# Fish_Feeder_Schematic.net
KiCad netlist of a schematic drawn in Altium Designer
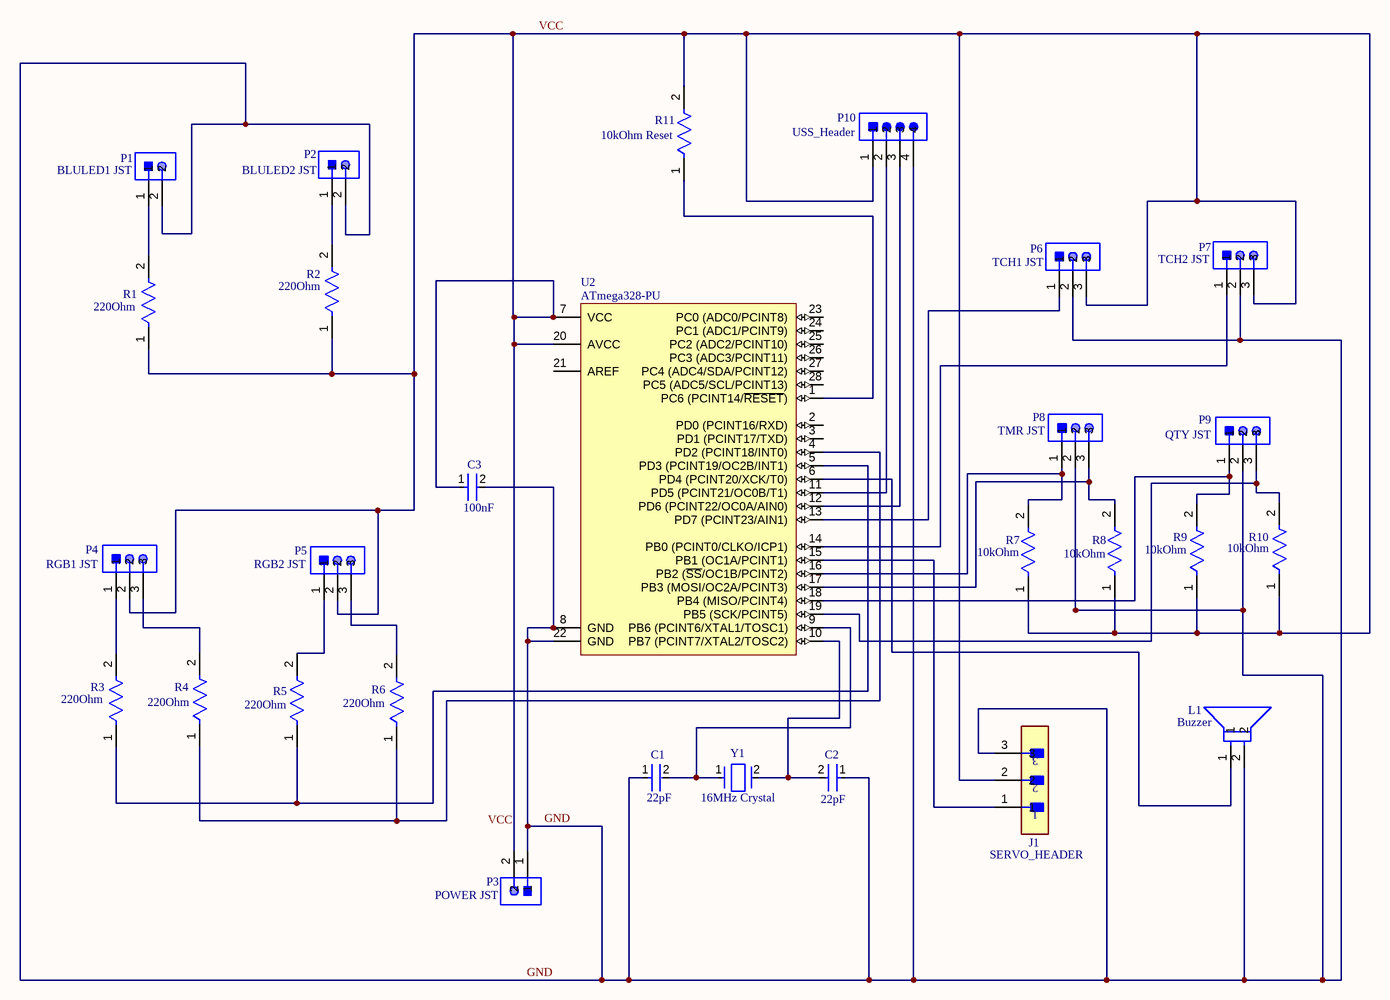
[diagram p0: Fish_Feeder_Schematic.SchDoc]

(export (version "E")
  (design (tool "Eeschema 10.0.6"))
  (components
    (comp (ref "C1")
      (value "22pF")
      (footprint "FP-VY1470-MFG")
      (description "CAP CER 2200PF 760VAC Y5U RADIAL")
      (fields (field (name "VOLTAGE") "500V") (field (name "TOLERANCE") "20%"))
      (libsource (lib "Altium Content Vault") (part "11868f565c42a9108669ba33697ecf6"))
    )
    (comp (ref "C2")
      (value "22pF")
      (footprint "FP-VY1470-MFG")
      (description "CAP CER 2200PF 760VAC Y5U RADIAL")
      (fields (field (name "VOLTAGE") "500V") (field (name "TOLERANCE") "20%"))
      (libsource (lib "Altium Content Vault") (part "11868f565c42a9108669ba33697ecf6"))
    )
    (comp (ref "C3")
      (value "100nF")
      (footprint "FP-VY1470-MFG")
      (description "CAP CER 2200PF 760VAC Y5U RADIAL")
      (fields (field (name "VOLTAGE") "500V") (field (name "TOLERANCE") "20%"))
      (libsource (lib "Altium Content Vault") (part "11868f565c42a9108669ba33697ecf6"))
    )
    (comp (ref "J1")
      (value "SERVO_HEADER")
      (footprint "FP-87224-3-MFG")
      (description "CONN HEADER VERT 3POS 2.54MM")
      (libsource (lib "Altium Content Vault") (part "0d3f023dd272f625e17a2be33dea85f"))
    )
    (comp (ref "L1")
      (value "Buzzer")
      (footprint "FP-PS1440P02BT-MFG")
      (description "AUDIO PIEZO TRANSDUCER 30V TH")
      (libsource (lib "Altium Content Vault") (part "5f581d31613f872430949aa526fd155"))
    )
    (comp (ref "P1")
      (value "BLULED1 JST")
      (footprint "JST-S2B-PH-K-S_V")
      (fields (field (name "TOLERANCE") "20%"))
      (libsource (lib "Altium Content Vault") (part "CN-1P-M-R2"))
    )
    (comp (ref "P2")
      (value "BLULED2 JST")
      (footprint "JST-S2B-PH-K-S_V")
      (fields (field (name "TOLERANCE") "20%"))
      (libsource (lib "Altium Content Vault") (part "CN-1P-M-R2"))
    )
    (comp (ref "P3")
      (value "POWER JST")
      (footprint "JST-S2B-PH-K-S_V")
      (fields (field (name "TOLERANCE") "20%"))
      (libsource (lib "") (part "CN-1P-M-R2_1"))
    )
    (comp (ref "P4")
      (value "RGB1 JST")
      (footprint "JST-B3B-PH-K-S-3_V")
      (fields (field (name "MANUFACTURER") "JST"))
      (libsource (lib "Altium Content Vault") (part "CN-1P-M-R3"))
    )
    (comp (ref "P5")
      (value "RGB2 JST")
      (footprint "JST-B3B-PH-K-S-3_V")
      (fields (field (name "MANUFACTURER") "JST"))
      (libsource (lib "Altium Content Vault") (part "CN-1P-M-R3"))
    )
    (comp (ref "P6")
      (value "TCH1 JST")
      (footprint "JST-B3B-PH-K-S-3_V")
      (fields (field (name "MANUFACTURER") "JST"))
      (libsource (lib "Altium Content Vault") (part "CN-1P-M-R3"))
    )
    (comp (ref "P7")
      (value "TCH2 JST")
      (footprint "JST-B3B-PH-K-S-3_V")
      (fields (field (name "MANUFACTURER") "JST"))
      (libsource (lib "Altium Content Vault") (part "CN-1P-M-R3"))
    )
    (comp (ref "P8")
      (value "TMR JST")
      (footprint "JST-B3B-PH-K-S-3_V")
      (fields (field (name "MANUFACTURER") "JST"))
      (libsource (lib "Altium Content Vault") (part "CN-1P-M-R3"))
    )
    (comp (ref "P9")
      (value "QTY JST")
      (footprint "JST-B3B-PH-K-S-3_V")
      (fields (field (name "MANUFACTURER") "JST"))
      (libsource (lib "Altium Content Vault") (part "CN-1P-M-R3"))
    )
    (comp (ref "P10")
      (value "USS_Header")
      (footprint "TECO-640456-4")
      (description "Male Header, Pitch 2.54 mm, 1 x 4 Position, Height 10.03 mm, Tail Length 3.56 mm, RoHS, Bulk")
      (fields (field (name "MANUFACTURER") "TE Connectivity"))
      (libsource (lib "Altium Content Vault") (part "CN-1P-M-R4"))
    )
    (comp (ref "R1")
      (value "220Ohm")
      (footprint "FP-CFR-25-MFG")
      (description "RES 10 OHM 1/4W 5% AXIAL")
      (fields (field (name "TOLERANCE") "5%"))
      (libsource (lib "Altium Content Vault") (part "1029c3af85768c4190bb7ad29bc67b5"))
    )
    (comp (ref "R2")
      (value "220Ohm")
      (footprint "FP-CFR-25-MFG")
      (description "RES 10 OHM 1/4W 5% AXIAL")
      (fields (field (name "TOLERANCE") "5%"))
      (libsource (lib "Altium Content Vault") (part "1029c3af85768c4190bb7ad29bc67b5"))
    )
    (comp (ref "R3")
      (value "220Ohm")
      (footprint "FP-CFR-25-MFG")
      (description "RES 10 OHM 1/4W 5% AXIAL")
      (fields (field (name "TOLERANCE") "5%"))
      (libsource (lib "Altium Content Vault") (part "1029c3af85768c4190bb7ad29bc67b5"))
    )
    (comp (ref "R4")
      (value "220Ohm")
      (footprint "FP-CFR-25-MFG")
      (description "RES 10 OHM 1/4W 5% AXIAL")
      (fields (field (name "TOLERANCE") "5%"))
      (libsource (lib "Altium Content Vault") (part "1029c3af85768c4190bb7ad29bc67b5"))
    )
    (comp (ref "R5")
      (value "220Ohm")
      (footprint "FP-CFR-25-MFG")
      (description "RES 10 OHM 1/4W 5% AXIAL")
      (fields (field (name "TOLERANCE") "5%"))
      (libsource (lib "Altium Content Vault") (part "1029c3af85768c4190bb7ad29bc67b5"))
    )
    (comp (ref "R6")
      (value "220Ohm")
      (footprint "FP-CFR-25-MFG")
      (description "RES 10 OHM 1/4W 5% AXIAL")
      (fields (field (name "TOLERANCE") "5%"))
      (libsource (lib "Altium Content Vault") (part "1029c3af85768c4190bb7ad29bc67b5"))
    )
    (comp (ref "R7")
      (value "10kOhm")
      (footprint "FP-CFR-25-MFG")
      (description "RES 10 OHM 1/4W 5% AXIAL")
      (fields (field (name "TOLERANCE") "5%"))
      (libsource (lib "Altium Content Vault") (part "1029c3af85768c4190bb7ad29bc67b5"))
    )
    (comp (ref "R8")
      (value "10kOhm")
      (footprint "FP-CFR-25-MFG")
      (description "RES 10 OHM 1/4W 5% AXIAL")
      (fields (field (name "TOLERANCE") "5%"))
      (libsource (lib "Altium Content Vault") (part "1029c3af85768c4190bb7ad29bc67b5"))
    )
    (comp (ref "R9")
      (value "10kOhm")
      (footprint "FP-CFR-25-MFG")
      (description "RES 10 OHM 1/4W 5% AXIAL")
      (fields (field (name "TOLERANCE") "5%"))
      (libsource (lib "Altium Content Vault") (part "1029c3af85768c4190bb7ad29bc67b5"))
    )
    (comp (ref "R10")
      (value "10kOhm")
      (footprint "FP-CFR-25-MFG")
      (description "RES 10 OHM 1/4W 5% AXIAL")
      (fields (field (name "TOLERANCE") "5%"))
      (libsource (lib "Altium Content Vault") (part "1029c3af85768c4190bb7ad29bc67b5"))
    )
    (comp (ref "R11")
      (value "10kOhm Reset")
      (footprint "FP-CFR-25-MFG")
      (description "RES 10 OHM 1/4W 5% AXIAL")
      (fields (field (name "TOLERANCE") "5%"))
      (libsource (lib "Altium Content Vault") (part "1029c3af85768c4190bb7ad29bc67b5"))
    )
    (comp (ref "U2")
      (value "ATmega328-PU")
      (footprint "28P3")
      (libsource (lib "Altium Content Vault") (part "MC-8B-ATM48-IL28"))
    )
    (comp (ref "Y1")
      (value "16MHz Crystal")
      (footprint "FP-ABL-MFG")
      (description "CRYSTAL 16.0000MHZ 18PF TH")
      (fields (field (name "TOLERANCE") "30ppm"))
      (libsource (lib "Altium Content Vault") (part "c23a69dc6c9e2f18f2079038eb95dd1"))
    )
  )
  (nets
    (net (code "1") (name "/GND") (class "Default")
      (node (ref "C1") (pin "1") (pinfunction "1_1") (pintype "passive"))
      (node (ref "C2") (pin "1") (pinfunction "1_1") (pintype "passive"))
      (node (ref "C3") (pin "2") (pinfunction "2_2") (pintype "passive"))
      (node (ref "J1") (pin "3") (pinfunction "3_3") (pintype "passive"))
      (node (ref "L1") (pin "2") (pinfunction "2_2") (pintype "passive"))
      (node (ref "P1") (pin "2") (pinfunction "2_2") (pintype "passive"))
      (node (ref "P10") (pin "4") (pinfunction "4_4") (pintype "passive"))
      (node (ref "P2") (pin "2") (pinfunction "2_2") (pintype "passive"))
      (node (ref "P3") (pin "1") (pinfunction "1_1") (pintype "passive"))
      (node (ref "P6") (pin "2") (pinfunction "2_2") (pintype "passive"))
      (node (ref "P7") (pin "2") (pinfunction "2_2") (pintype "passive"))
      (node (ref "P8") (pin "2") (pinfunction "2_2") (pintype "passive"))
      (node (ref "P9") (pin "2") (pinfunction "2_2") (pintype "passive"))
      (node (ref "U2") (pin "22") (pinfunction "GND_22") (pintype "power_in"))
      (node (ref "U2") (pin "8") (pinfunction "GND_8") (pintype "power_in"))
    )
    (net (code "2") (name "/VCC") (class "Default")
      (node (ref "C3") (pin "1") (pinfunction "1_1") (pintype "passive"))
      (node (ref "J1") (pin "2") (pinfunction "2_2") (pintype "passive"))
      (node (ref "P10") (pin "1") (pinfunction "1_1") (pintype "passive"))
      (node (ref "P3") (pin "2") (pinfunction "2_2") (pintype "passive"))
      (node (ref "P4") (pin "2") (pinfunction "2_2") (pintype "passive"))
      (node (ref "P5") (pin "2") (pinfunction "2_2") (pintype "passive"))
      (node (ref "P6") (pin "3") (pinfunction "3_3") (pintype "passive"))
      (node (ref "P7") (pin "3") (pinfunction "3_3") (pintype "passive"))
      (node (ref "R1") (pin "1") (pinfunction "1_1") (pintype "passive"))
      (node (ref "R10") (pin "1") (pinfunction "1_1") (pintype "passive"))
      (node (ref "R11") (pin "2") (pinfunction "2_2") (pintype "passive"))
      (node (ref "R2") (pin "1") (pinfunction "1_1") (pintype "passive"))
      (node (ref "R7") (pin "1") (pinfunction "1_1") (pintype "passive"))
      (node (ref "R8") (pin "1") (pinfunction "1_1") (pintype "passive"))
      (node (ref "R9") (pin "1") (pinfunction "1_1") (pintype "passive"))
      (node (ref "U2") (pin "20") (pinfunction "AVCC_20") (pintype "power_in"))
      (node (ref "U2") (pin "7") (pinfunction "VCC_7") (pintype "power_in"))
    )
    (net (code "3") (name "Net-(P1-Pad1)") (class "Default")
      (node (ref "P1") (pin "1") (pinfunction "1_1") (pintype "passive"))
      (node (ref "R1") (pin "2") (pinfunction "2_2") (pintype "passive"))
    )
    (net (code "4") (name "Net-(P2-Pad1)") (class "Default")
      (node (ref "P2") (pin "1") (pinfunction "1_1") (pintype "passive"))
      (node (ref "R2") (pin "2") (pinfunction "2_2") (pintype "passive"))
    )
    (net (code "5") (name "Net-(P4-Pad1)") (class "Default")
      (node (ref "P4") (pin "1") (pinfunction "1_1") (pintype "passive"))
      (node (ref "R3") (pin "2") (pinfunction "2_2") (pintype "passive"))
    )
    (net (code "6") (name "Net-(P4-Pad3)") (class "Default")
      (node (ref "P4") (pin "3") (pinfunction "3_3") (pintype "passive"))
      (node (ref "R4") (pin "2") (pinfunction "2_2") (pintype "passive"))
    )
    (net (code "7") (name "Net-(P5-Pad1)") (class "Default")
      (node (ref "P5") (pin "1") (pinfunction "1_1") (pintype "passive"))
      (node (ref "R5") (pin "2") (pinfunction "2_2") (pintype "passive"))
    )
    (net (code "8") (name "Net-(P5-Pad3)") (class "Default")
      (node (ref "P5") (pin "3") (pinfunction "3_3") (pintype "passive"))
      (node (ref "R6") (pin "2") (pinfunction "2_2") (pintype "passive"))
    )
    (net (code "9") (name "Net-(U2-PB0_(PCINT0{slash}CLKO{slash}ICP1))") (class "Default")
      (node (ref "P7") (pin "1") (pinfunction "1_1") (pintype "passive"))
      (node (ref "U2") (pin "14") (pinfunction "PB0_(PCINT0/CLKO/ICP1)_14") (pintype "bidirectional"))
    )
    (net (code "10") (name "Net-(U2-PB1_(OC1A{slash}PCINT1))") (class "Default")
      (node (ref "J1") (pin "1") (pinfunction "1_1") (pintype "passive"))
      (node (ref "U2") (pin "15") (pinfunction "PB1_(OC1A/PCINT1)_15") (pintype "bidirectional"))
    )
    (net (code "11") (name "Net-(U2-PB2_(~{SS}{slash}OC1B{slash}PCINT2))") (class "Default")
      (node (ref "P8") (pin "1") (pinfunction "1_1") (pintype "passive"))
      (node (ref "R7") (pin "2") (pinfunction "2_2") (pintype "passive"))
      (node (ref "U2") (pin "16") (pinfunction "PB2_(~{SS}/OC1B/PCINT2)_16") (pintype "bidirectional"))
    )
    (net (code "12") (name "Net-(U2-PB3_(MOSI{slash}OC2A{slash}PCINT3))") (class "Default")
      (node (ref "P8") (pin "3") (pinfunction "3_3") (pintype "passive"))
      (node (ref "R8") (pin "2") (pinfunction "2_2") (pintype "passive"))
      (node (ref "U2") (pin "17") (pinfunction "PB3_(MOSI/OC2A/PCINT3)_17") (pintype "bidirectional"))
    )
    (net (code "13") (name "Net-(U2-PB4_(MISO{slash}PCINT4))") (class "Default")
      (node (ref "P9") (pin "1") (pinfunction "1_1") (pintype "passive"))
      (node (ref "R9") (pin "2") (pinfunction "2_2") (pintype "passive"))
      (node (ref "U2") (pin "18") (pinfunction "PB4_(MISO/PCINT4)_18") (pintype "bidirectional"))
    )
    (net (code "14") (name "Net-(U2-PB5_(SCK{slash}PCINT5))") (class "Default")
      (node (ref "P9") (pin "3") (pinfunction "3_3") (pintype "passive"))
      (node (ref "R10") (pin "2") (pinfunction "2_2") (pintype "passive"))
      (node (ref "U2") (pin "19") (pinfunction "PB5_(SCK/PCINT5)_19") (pintype "bidirectional"))
    )
    (net (code "15") (name "Net-(U2-PB6_(PCINT6{slash}XTAL1{slash}TOSC1))") (class "Default")
      (node (ref "C1") (pin "2") (pinfunction "2_2") (pintype "passive"))
      (node (ref "U2") (pin "9") (pinfunction "PB6_(PCINT6/XTAL1/TOSC1)_9") (pintype "bidirectional"))
      (node (ref "Y1") (pin "1") (pinfunction "1_1") (pintype "passive"))
    )
    (net (code "16") (name "Net-(U2-PB7_(PCINT7{slash}XTAL2{slash}TOSC2))") (class "Default")
      (node (ref "C2") (pin "2") (pinfunction "2_2") (pintype "passive"))
      (node (ref "U2") (pin "10") (pinfunction "PB7_(PCINT7/XTAL2/TOSC2)_10") (pintype "bidirectional"))
      (node (ref "Y1") (pin "2") (pinfunction "2_2") (pintype "passive"))
    )
    (net (code "17") (name "Net-(U2-PC6_(PCINT14{slash}~{RESET}))") (class "Default")
      (node (ref "R11") (pin "1") (pinfunction "1_1") (pintype "passive"))
      (node (ref "U2") (pin "1") (pinfunction "PC6_(PCINT14/~{RESET})_1") (pintype "bidirectional"))
    )
    (net (code "18") (name "Net-(U2-PD2_(PCINT18{slash}INT0))") (class "Default")
      (node (ref "R4") (pin "1") (pinfunction "1_1") (pintype "passive"))
      (node (ref "R6") (pin "1") (pinfunction "1_1") (pintype "passive"))
      (node (ref "U2") (pin "4") (pinfunction "PD2_(PCINT18/INT0)_4") (pintype "bidirectional"))
    )
    (net (code "19") (name "Net-(U2-PD3_(PCINT19{slash}OC2B{slash}INT1))") (class "Default")
      (node (ref "R3") (pin "1") (pinfunction "1_1") (pintype "passive"))
      (node (ref "R5") (pin "1") (pinfunction "1_1") (pintype "passive"))
      (node (ref "U2") (pin "5") (pinfunction "PD3_(PCINT19/OC2B/INT1)_5") (pintype "bidirectional"))
    )
    (net (code "20") (name "Net-(U2-PD4_(PCINT20{slash}XCK{slash}T0))") (class "Default")
      (node (ref "L1") (pin "1") (pinfunction "1_1") (pintype "passive"))
      (node (ref "U2") (pin "6") (pinfunction "PD4_(PCINT20/XCK/T0)_6") (pintype "bidirectional"))
    )
    (net (code "21") (name "Net-(U2-PD5_(PCINT21{slash}OC0B{slash}T1))") (class "Default")
      (node (ref "P10") (pin "2") (pinfunction "2_2") (pintype "passive"))
      (node (ref "U2") (pin "11") (pinfunction "PD5_(PCINT21/OC0B/T1)_11") (pintype "bidirectional"))
    )
    (net (code "22") (name "Net-(U2-PD6_(PCINT22{slash}OC0A{slash}AIN0))") (class "Default")
      (node (ref "P10") (pin "3") (pinfunction "3_3") (pintype "passive"))
      (node (ref "U2") (pin "12") (pinfunction "PD6_(PCINT22/OC0A/AIN0)_12") (pintype "bidirectional"))
    )
    (net (code "23") (name "Net-(U2-PD7_(PCINT23{slash}AIN1))") (class "Default")
      (node (ref "P6") (pin "1") (pinfunction "1_1") (pintype "passive"))
      (node (ref "U2") (pin "13") (pinfunction "PD7_(PCINT23/AIN1)_13") (pintype "bidirectional"))
    )
    (net (code "24") (name "unconnected-(U2-AREF-Pad21)") (class "Default")
      (node (ref "U2") (pin "21") (pinfunction "AREF_21") (pintype "power_in"))
    )
    (net (code "25") (name "unconnected-(U2-PC0_(ADC0{slash}PCINT8)-Pad23)") (class "Default")
      (node (ref "U2") (pin "23") (pinfunction "PC0_(ADC0/PCINT8)_23") (pintype "bidirectional"))
    )
    (net (code "26") (name "unconnected-(U2-PC1_(ADC1{slash}PCINT9)-Pad24)") (class "Default")
      (node (ref "U2") (pin "24") (pinfunction "PC1_(ADC1/PCINT9)_24") (pintype "bidirectional"))
    )
    (net (code "27") (name "unconnected-(U2-PC2_(ADC2{slash}PCINT10)-Pad25)") (class "Default")
      (node (ref "U2") (pin "25") (pinfunction "PC2_(ADC2/PCINT10)_25") (pintype "bidirectional"))
    )
    (net (code "28") (name "unconnected-(U2-PC3_(ADC3{slash}PCINT11)-Pad26)") (class "Default")
      (node (ref "U2") (pin "26") (pinfunction "PC3_(ADC3/PCINT11)_26") (pintype "bidirectional"))
    )
    (net (code "29") (name "unconnected-(U2-PC4_(ADC4{slash}SDA{slash}PCINT12)-Pad27)") (class "Default")
      (node (ref "U2") (pin "27") (pinfunction "PC4_(ADC4/SDA/PCINT12)_27") (pintype "bidirectional"))
    )
    (net (code "30") (name "unconnected-(U2-PC5_(ADC5{slash}SCL{slash}PCINT13)-Pad28)") (class "Default")
      (node (ref "U2") (pin "28") (pinfunction "PC5_(ADC5/SCL/PCINT13)_28") (pintype "bidirectional"))
    )
    (net (code "31") (name "unconnected-(U2-PD0_(PCINT16{slash}RXD)-Pad2)") (class "Default")
      (node (ref "U2") (pin "2") (pinfunction "PD0_(PCINT16/RXD)_2") (pintype "bidirectional"))
    )
    (net (code "32") (name "unconnected-(U2-PD1_(PCINT17{slash}TXD)-Pad3)") (class "Default")
      (node (ref "U2") (pin "3") (pinfunction "PD1_(PCINT17/TXD)_3") (pintype "bidirectional"))
    )
  )
)
